# 4_Channel_ADC.net
KiCad netlist of a schematic drawn in Altium Designer
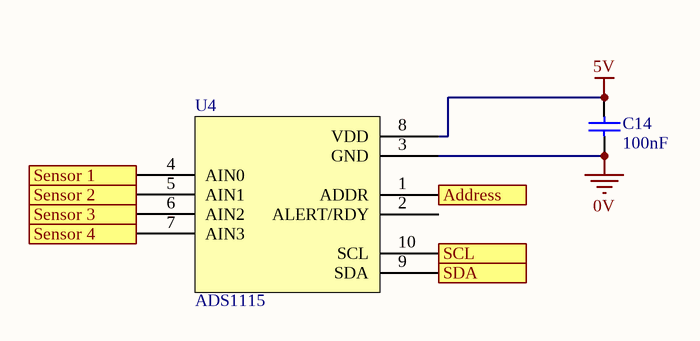
[diagram p0: 4 Channel ADC.SchDoc]

(export (version "E")
  (design (tool "Eeschema 10.0.6"))
  (components
    (comp (ref "C14")
      (value "100nF")
      (footprint "0805")
      (fields
        (field (name "PART NUMBER") "GCM21BR71E104KA37L")
        (field (name "TOLERANCE") "10%")
        (field (name "MANUFACTURER") "muRata")
      )
      (libsource (lib "ts_20-standard-library") (part "Capacitor"))
    )
    (comp (ref "U4")
      (value "ADS1115")
      (footprint "TI 10-VSSOP")
      (description "16 Bit Analog to Digital Converter 2, 4 Input 1 Sigma-Delta 10-VSSOP")
      (fields
        (field (name "MANUFACTURER") "Texas Instruments")
        (field (name "DIGIKEY PART NUMBER") "296-38849-1-ND")
      )
      (libsource (lib "ts_20-standard-library") (part "ADS1115"))
    )
  )
  (nets
    (net (code "1") (name "/Address") (class "Default")
      (node (ref "U4") (pin "1") (pinfunction "ADDR_1") (pintype "passive"))
    )
    (net (code "2") (name "/SCL") (class "Default")
      (node (ref "U4") (pin "10") (pinfunction "SCL_10") (pintype "passive"))
    )
    (net (code "3") (name "/SDA") (class "Default")
      (node (ref "U4") (pin "9") (pinfunction "SDA_9") (pintype "passive"))
    )
    (net (code "4") (name "/Sensor 1") (class "Default")
      (node (ref "U4") (pin "4") (pinfunction "AIN0_4") (pintype "passive"))
    )
    (net (code "5") (name "/Sensor 2") (class "Default")
      (node (ref "U4") (pin "5") (pinfunction "AIN1_5") (pintype "passive"))
    )
    (net (code "6") (name "/Sensor 3") (class "Default")
      (node (ref "U4") (pin "6") (pinfunction "AIN2_6") (pintype "passive"))
    )
    (net (code "7") (name "/Sensor 4") (class "Default")
      (node (ref "U4") (pin "7") (pinfunction "AIN3_7") (pintype "passive"))
    )
    (net (code "8") (name "0V") (class "Default")
      (node (ref "C14") (pin "1") (pinfunction "1_1") (pintype "passive"))
      (node (ref "U4") (pin "3") (pinfunction "GND_3") (pintype "passive"))
    )
    (net (code "9") (name "5V") (class "Default")
      (node (ref "C14") (pin "2") (pinfunction "2_2") (pintype "passive"))
      (node (ref "U4") (pin "8") (pinfunction "VDD_8") (pintype "passive"))
    )
    (net (code "10") (name "unconnected-(U4-ALERT{slash}RDY-Pad2)") (class "Default")
      (node (ref "U4") (pin "2") (pinfunction "ALERT/RDY_2") (pintype "passive"))
    )
  )
)
